# lane.net
KiCad netlist of a schematic drawn in Altium Designer
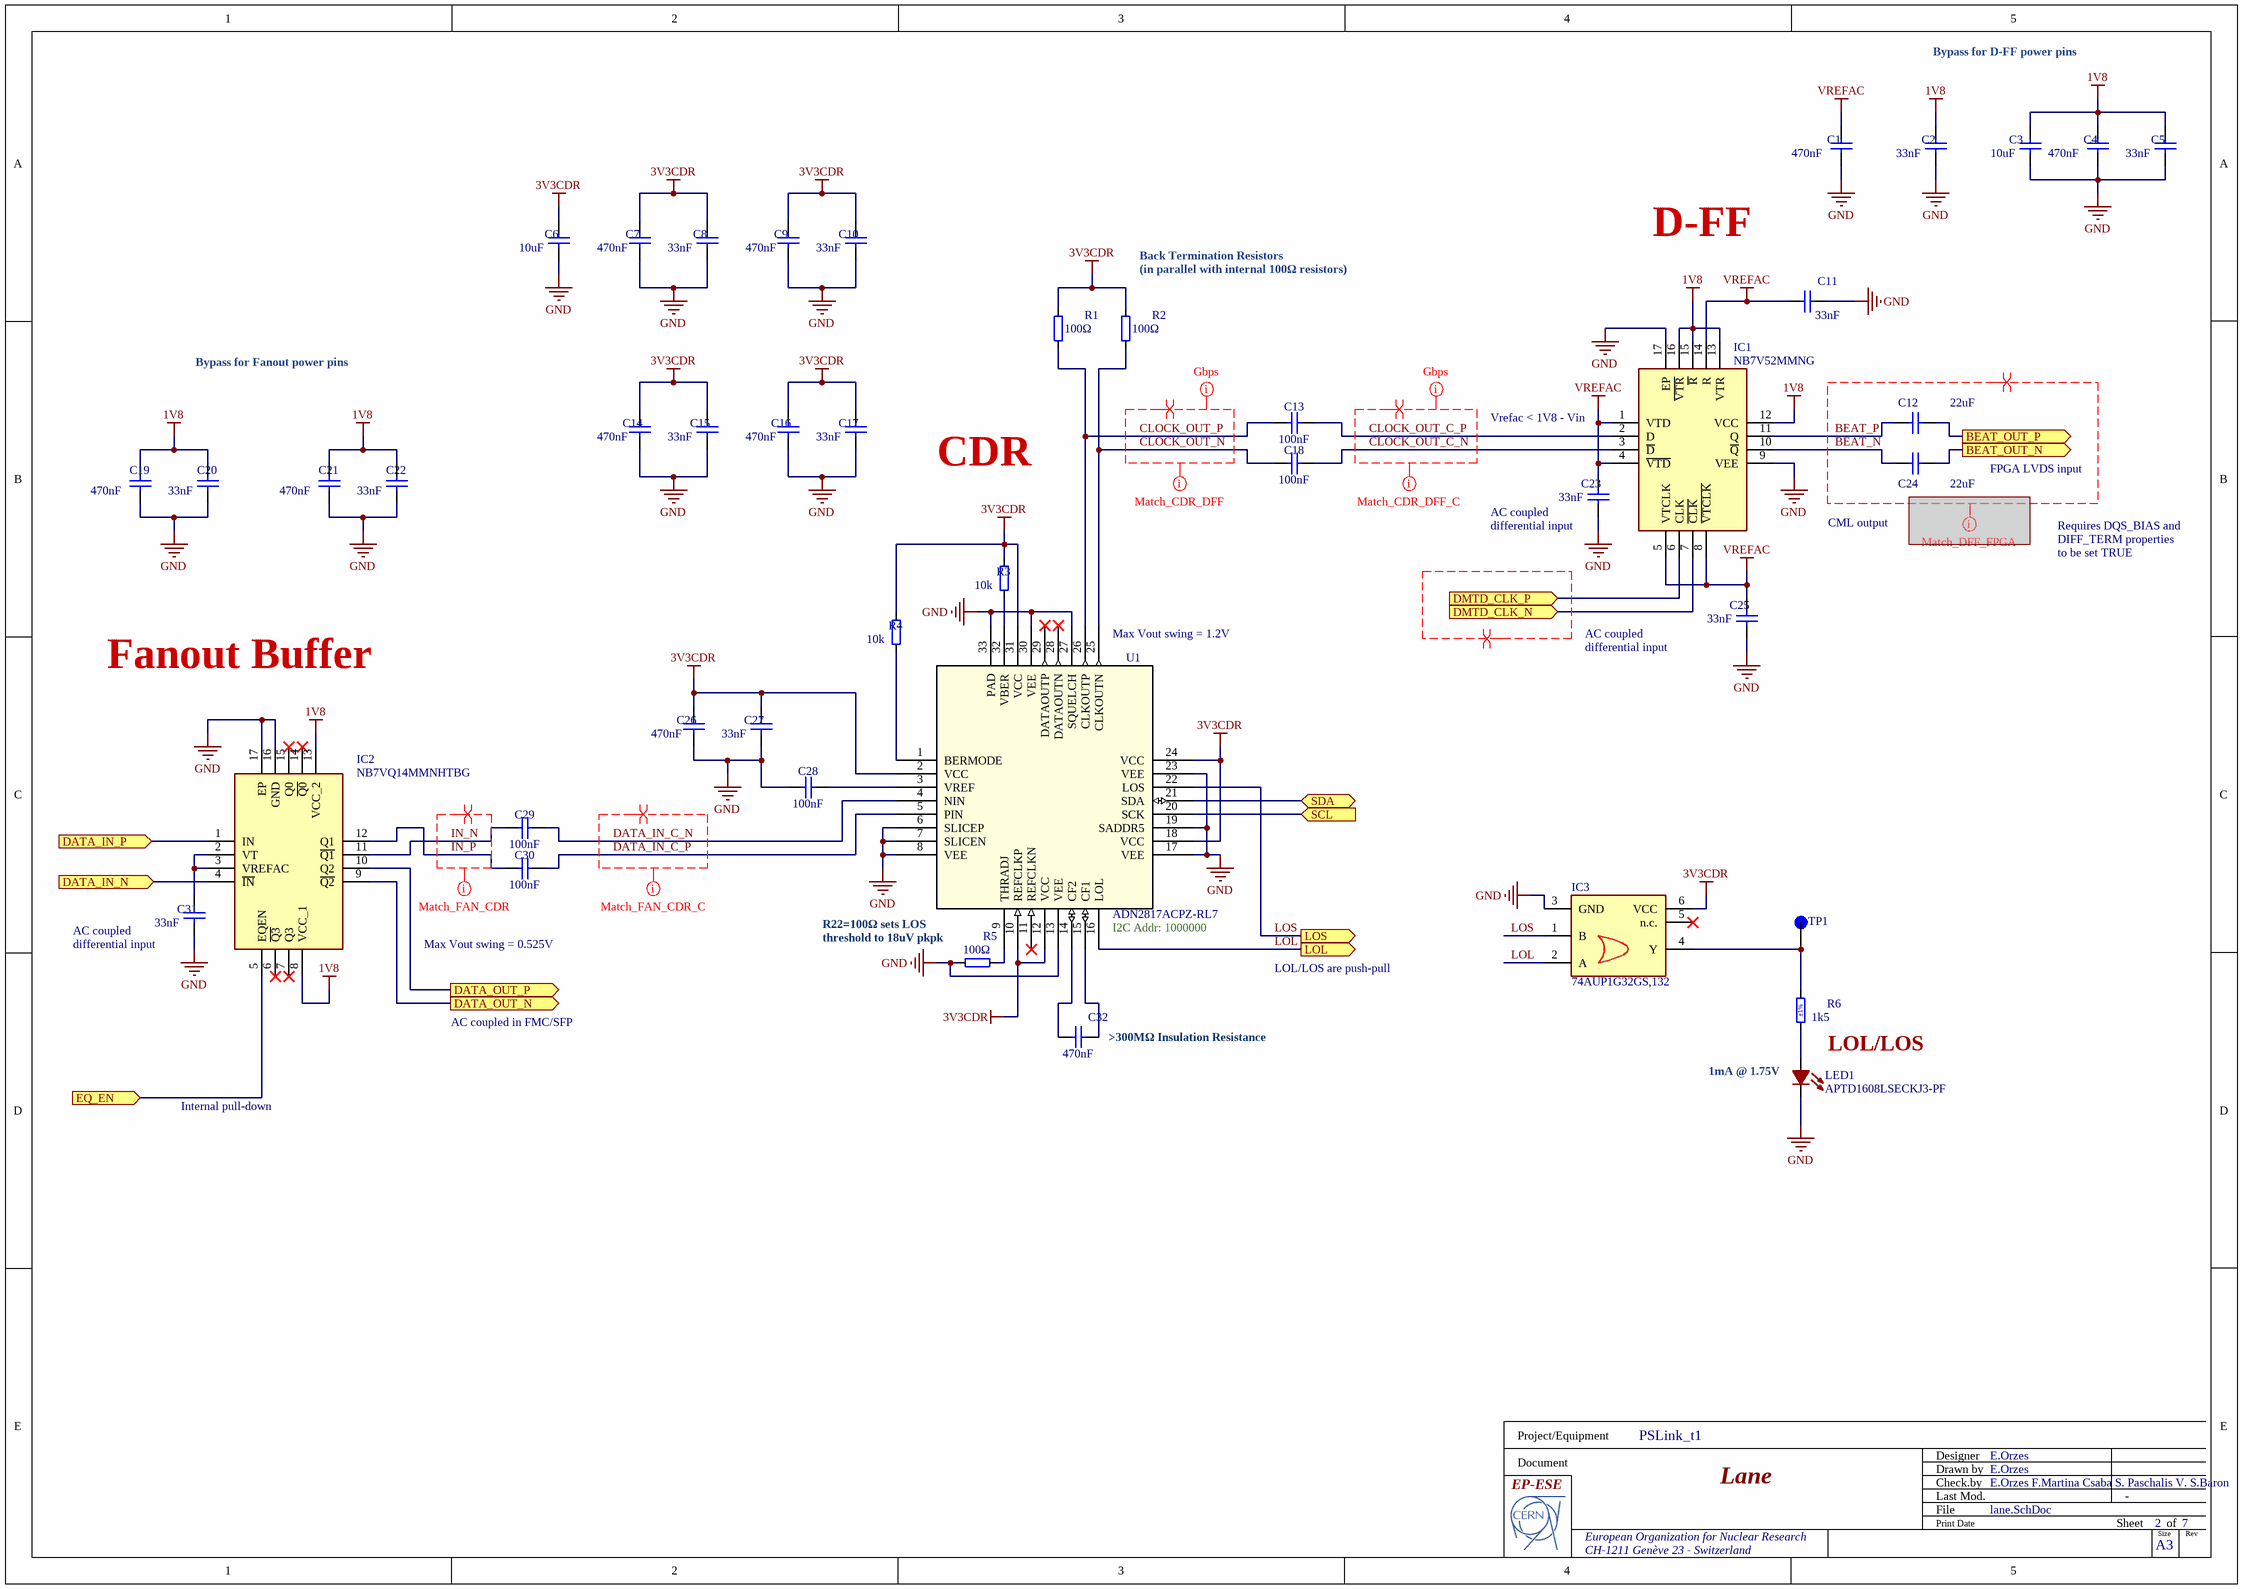
[diagram p0: lane.SchDoc]

(export (version "E")
  (design (tool "Eeschema 10.0.6"))
  (components
    (comp (ref "C1")
      (value "470nF")
      (footprint "CAPC0510X04N")
      (description "LLL153C70G474ME17")
      (libsource (lib "auxiliary_library") (part "Capacitor - non polarized"))
    )
    (comp (ref "C2")
      (value "33nF")
      (footprint "LLL03TR61E333KE01")
      (description "LLL03TR61E333KE01")
      (libsource (lib "auxiliary_library") (part "Capacitor - non polarized"))
    )
    (comp (ref "C3")
      (value "10uF")
      (footprint "CAPC1608X87N")
      (description "C1608X5R1E106M080AC")
      (fields
        (field (name "PART NUMBER") "CC0603_10UF_6.3V_20%_X5R")
        (field (name "VOLTAGE") "6.3V")
        (field (name "AUTHOR") "CERN DEM JLC")
      )
      (libsource (lib "Capacitors") (part "Capacitor - non polarized"))
    )
    (comp (ref "C4")
      (value "470nF")
      (footprint "CAPC0510X04N")
      (description "LLL153C70G474ME17")
      (libsource (lib "auxiliary_library") (part "Capacitor - non polarized"))
    )
    (comp (ref "C5")
      (value "33nF")
      (footprint "LLL03TR61E333KE01")
      (description "LLL03TR61E333KE01")
      (libsource (lib "auxiliary_library") (part "Capacitor - non polarized"))
    )
    (comp (ref "C6")
      (value "10uF")
      (footprint "CAPC1608X87N")
      (description "C1608X5R1E106M080AC")
      (fields
        (field (name "PART NUMBER") "CC0603_10UF_6.3V_20%_X5R")
        (field (name "VOLTAGE") "6.3V")
        (field (name "AUTHOR") "CERN DEM JLC")
      )
      (libsource (lib "Capacitors") (part "Capacitor - non polarized"))
    )
    (comp (ref "C7")
      (value "470nF")
      (footprint "CAPC0510X04N")
      (description "LLL153C70G474ME17")
      (libsource (lib "auxiliary_library") (part "Capacitor - non polarized"))
    )
    (comp (ref "C8")
      (value "33nF")
      (footprint "LLL03TR61E333KE01")
      (description "LLL03TR61E333KE01")
      (libsource (lib "auxiliary_library") (part "Capacitor - non polarized"))
    )
    (comp (ref "C9")
      (value "470nF")
      (footprint "CAPC0510X04N")
      (description "LLL153C70G474ME17")
      (libsource (lib "auxiliary_library") (part "Capacitor - non polarized"))
    )
    (comp (ref "C10")
      (value "33nF")
      (footprint "LLL03TR61E333KE01")
      (description "LLL03TR61E333KE01")
      (libsource (lib "auxiliary_library") (part "Capacitor - non polarized"))
    )
    (comp (ref "C11")
      (value "33nF")
      (footprint "LLL03TR61E333KE01")
      (description "LLL03TR61E333KE01")
      (libsource (lib "auxiliary_library") (part "Capacitor - non polarized"))
    )
    (comp (ref "C12")
      (value "22uF")
      (footprint "MURATA_HI_DENSITY_0402_CAP")
      (description "GRM155R60J226ME11")
      (libsource (lib "schLib") (part "C0402-22uF-high-density"))
    )
    (comp (ref "C13")
      (value "100nF")
      (footprint "MURATA_HI_DENSITY_0201")
      (description "GRM033R61C104KE14")
      (libsource (lib "schLib") (part "C0201-100nF-high-density"))
    )
    (comp (ref "C14")
      (value "470nF")
      (footprint "CAPC0510X04N")
      (description "LLL153C70G474ME17")
      (libsource (lib "auxiliary_library") (part "Capacitor - non polarized"))
    )
    (comp (ref "C15")
      (value "33nF")
      (footprint "LLL03TR61E333KE01")
      (description "LLL03TR61E333KE01")
      (libsource (lib "auxiliary_library") (part "Capacitor - non polarized"))
    )
    (comp (ref "C16")
      (value "470nF")
      (footprint "CAPC0510X04N")
      (description "LLL153C70G474ME17")
      (libsource (lib "auxiliary_library") (part "Capacitor - non polarized"))
    )
    (comp (ref "C17")
      (value "33nF")
      (footprint "LLL03TR61E333KE01")
      (description "LLL03TR61E333KE01")
      (libsource (lib "auxiliary_library") (part "Capacitor - non polarized"))
    )
    (comp (ref "C18")
      (value "100nF")
      (footprint "MURATA_HI_DENSITY_0201")
      (description "GRM033R61C104KE14")
      (libsource (lib "schLib") (part "C0201-100nF-high-density"))
    )
    (comp (ref "C19")
      (value "470nF")
      (footprint "CAPC0510X04N")
      (description "LLL153C70G474ME17")
      (libsource (lib "auxiliary_library") (part "Capacitor - non polarized"))
    )
    (comp (ref "C20")
      (value "33nF")
      (footprint "LLL03TR61E333KE01")
      (description "LLL03TR61E333KE01")
      (libsource (lib "auxiliary_library") (part "Capacitor - non polarized"))
    )
    (comp (ref "C21")
      (value "470nF")
      (footprint "CAPC0510X04N")
      (description "LLL153C70G474ME17")
      (libsource (lib "auxiliary_library") (part "Capacitor - non polarized"))
    )
    (comp (ref "C22")
      (value "33nF")
      (footprint "LLL03TR61E333KE01")
      (description "LLL03TR61E333KE01")
      (libsource (lib "auxiliary_library") (part "Capacitor - non polarized"))
    )
    (comp (ref "C23")
      (value "33nF")
      (footprint "LLL03TR61E333KE01")
      (description "LLL03TR61E333KE01")
      (libsource (lib "auxiliary_library") (part "Capacitor - non polarized"))
    )
    (comp (ref "C24")
      (value "22uF")
      (footprint "MURATA_HI_DENSITY_0402_CAP")
      (description "GRM155R60J226ME11")
      (libsource (lib "schLib") (part "C0402-22uF-high-density"))
    )
    (comp (ref "C25")
      (value "33nF")
      (footprint "LLL03TR61E333KE01")
      (description "LLL03TR61E333KE01")
      (libsource (lib "auxiliary_library") (part "Capacitor - non polarized"))
    )
    (comp (ref "C26")
      (value "470nF")
      (footprint "CAPC0510X04N")
      (description "LLL153C70G474ME17")
      (libsource (lib "auxiliary_library") (part "Capacitor - non polarized"))
    )
    (comp (ref "C27")
      (value "33nF")
      (footprint "LLL03TR61E333KE01")
      (description "LLL03TR61E333KE01")
      (libsource (lib "auxiliary_library") (part "Capacitor - non polarized"))
    )
    (comp (ref "C28")
      (value "100nF")
      (footprint "MURATA_HI_DENSITY_0201")
      (description "GRM033R61C104KE14")
      (libsource (lib "schLib") (part "C0201-100nF-high-density"))
    )
    (comp (ref "C29")
      (value "100nF")
      (footprint "MURATA_HI_DENSITY_0201")
      (description "GRM033R61C104KE14")
      (libsource (lib "schLib") (part "C0201-100nF-high-density"))
    )
    (comp (ref "C30")
      (value "100nF")
      (footprint "MURATA_HI_DENSITY_0201")
      (description "GRM033R61C104KE14")
      (libsource (lib "schLib") (part "C0201-100nF-high-density"))
    )
    (comp (ref "C31")
      (value "33nF")
      (footprint "LLL03TR61E333KE01")
      (description "LLL03TR61E333KE01")
      (libsource (lib "auxiliary_library") (part "Capacitor - non polarized"))
    )
    (comp (ref "C32")
      (value "470nF")
      (footprint "CAPC2013X140N")
      (description "GCM21BR71H474KA55L")
      (fields
        (field (name "PART NUMBER") "CC0805_470NF_50V_10%_X7R_MURATA_GCM21BR71H474KA55L")
        (field (name "VOLTAGE") "50V")
        (field (name "AUTHOR") "CERN DEM JLC")
      )
      (libsource (lib "Capacitors") (part "Capacitor - non polarized"))
    )
    (comp (ref "IC1")
      (value "NB7V52MMNG")
      (footprint "SamacSys:QFN50P300X300X100-17N")
      (description "Integrated Circuit")
      (fields (field (name "MOUSER PART NUMBER") "863-NB7V52MMNG"))
      (libsource (lib "SamacSys") (part "NB7V52MMNG"))
    )
    (comp (ref "IC2")
      (value "NB7VQ14MMNHTBG")
      (footprint "SamacSys:QFN50P300X300X100-17N")
      (description "Integrated Circuit")
      (fields (field (name "MOUSER PART NUMBER") "863-NB7VQ14MMNHTBG"))
      (libsource (lib "*") (part "NB7VQ14MMNHTBG"))
    )
    (comp (ref "IC3")
      (value "74AUP1G32GS,132")
      (footprint "SamacSys:74LVC1G3157GS132")
      (description "Integrated Circuit")
      (fields (field (name "MOUSER PART NUMBER") "771-74AUP1G32GS132"))
      (libsource (lib "SamacSys") (part "74AUP1G32GS,132"))
    )
    (comp (ref "LED1")
      (value "APTD1608LSECKJ3-PF")
      (footprint "APTD1608LSECKJ3-PF:LED_APTD1608LSECKJ3-PF_KNB")
      (description "Led Red 0603 2mA 1.8V 50mcd 84mW")
      (libsource (lib "APTD1608LSECKJ3-PF") (part "APTD1608LSECKJ3-PF"))
    )
    (comp (ref "R1")
      (value "100Ω")
      (footprint "MURATA_HI_DENSITY_0201")
      (description "Resistor")
      (libsource (lib "schLib") (part "R0201-100ohm-high-density"))
    )
    (comp (ref "R2")
      (value "100Ω")
      (footprint "MURATA_HI_DENSITY_0201")
      (description "Resistor")
      (libsource (lib "schLib") (part "R0201-100ohm-high-density"))
    )
    (comp (ref "R3")
      (value "10k")
      (footprint "MURATA_HI_DENSITY_0201")
      (description "Resistor 10k")
      (libsource (lib "schLib") (part "R0201-100ohm-high-density"))
    )
    (comp (ref "R4")
      (value "10k")
      (footprint "MURATA_HI_DENSITY_0201")
      (description "Resistor 10k")
      (libsource (lib "schLib") (part "R0201-100ohm-high-density"))
    )
    (comp (ref "R5")
      (value "100Ω")
      (footprint "MURATA_HI_DENSITY_0201")
      (description "Resistor")
      (libsource (lib "schLib") (part "R0201-100ohm-high-density"))
    )
    (comp (ref "R6")
      (value "1k5")
      (footprint "RESC1005X40N")
      (description "Resistor - 1%")
      (fields
        (field (name "TOLERANCE") "±1%")
        (field (name "PART NUMBER") "R0402_1K5_1%_0.0625W_100PPM")
        (field (name "POWER") "0.0625W")
        (field (name "AUTHOR") "CERN DEM JLC")
      )
      (libsource (lib "Resistors") (part "Resistor - 1%"))
    )
    (comp (ref "TP1")
      (value "RCU-0C")
      (footprint "TP+195X110")
      (fields (field (name "MF") "{'manufacturer': u'TE Connectivity AMP Connectors'}"))
      (libsource (lib "RCU-0C") (part "RCU-0C"))
    )
    (comp (ref "U1")
      (value "ADN2817ACPZ-RL7")
      (footprint "CP_32_11_ADI")
      (description "CDR")
      (libsource (lib "ADN2817ACPZ-RL7") (part "ADN2817ACPZ-RL7"))
    )
  )
  (nets
    (net (code "1") (name "/BEAT_N") (class "Default")
      (node (ref "C24") (pin "2") (pinfunction "2_2") (pintype "passive"))
      (node (ref "IC1") (pin "10") (pinfunction "~{Q}_10") (pintype "passive"))
    )
    (net (code "2") (name "/BEAT_OUT_N") (class "Default")
      (node (ref "C24") (pin "1") (pinfunction "1_1") (pintype "passive"))
    )
    (net (code "3") (name "/BEAT_OUT_P") (class "Default")
      (node (ref "C12") (pin "1") (pinfunction "1_1") (pintype "passive"))
    )
    (net (code "4") (name "/BEAT_P") (class "Default")
      (node (ref "C12") (pin "2") (pinfunction "2_2") (pintype "passive"))
      (node (ref "IC1") (pin "11") (pinfunction "Q_11") (pintype "passive"))
    )
    (net (code "5") (name "/CLOCK_OUT_C_N") (class "Default")
      (node (ref "C18") (pin "2") (pinfunction "2_2") (pintype "passive"))
      (node (ref "IC1") (pin "3") (pinfunction "~{D}_3") (pintype "passive"))
    )
    (net (code "6") (name "/CLOCK_OUT_C_P") (class "Default")
      (node (ref "C13") (pin "2") (pinfunction "2_2") (pintype "passive"))
      (node (ref "IC1") (pin "2") (pinfunction "D_2") (pintype "passive"))
    )
    (net (code "7") (name "/CLOCK_OUT_N") (class "Default")
      (node (ref "C18") (pin "1") (pinfunction "1_1") (pintype "passive"))
      (node (ref "R2") (pin "1") (pinfunction "1_1") (pintype "passive"))
      (node (ref "U1") (pin "25") (pinfunction "CLKOUTN_25") (pintype "output"))
    )
    (net (code "8") (name "/CLOCK_OUT_P") (class "Default")
      (node (ref "C13") (pin "1") (pinfunction "1_1") (pintype "passive"))
      (node (ref "R1") (pin "1") (pinfunction "1_1") (pintype "passive"))
      (node (ref "U1") (pin "26") (pinfunction "CLKOUTP_26") (pintype "output"))
    )
    (net (code "9") (name "/DATA_IN_C_N") (class "Default")
      (node (ref "C29") (pin "2") (pinfunction "2_2") (pintype "passive"))
      (node (ref "U1") (pin "4") (pinfunction "NIN_4") (pintype "passive"))
    )
    (net (code "10") (name "/DATA_IN_C_P") (class "Default")
      (node (ref "C30") (pin "2") (pinfunction "2_2") (pintype "passive"))
      (node (ref "U1") (pin "5") (pinfunction "PIN_5") (pintype "passive"))
    )
    (net (code "11") (name "/DATA_IN_N") (class "Default")
      (node (ref "IC2") (pin "4") (pinfunction "~{IN}_4") (pintype "passive"))
    )
    (net (code "12") (name "/DATA_IN_P") (class "Default")
      (node (ref "IC2") (pin "1") (pinfunction "IN_1") (pintype "passive"))
    )
    (net (code "13") (name "/DATA_OUT_N") (class "Default")
      (node (ref "IC2") (pin "9") (pinfunction "~{Q2}_9") (pintype "passive"))
    )
    (net (code "14") (name "/DATA_OUT_P") (class "Default")
      (node (ref "IC2") (pin "10") (pinfunction "Q2_10") (pintype "passive"))
    )
    (net (code "15") (name "/DMTD_CLK_N") (class "Default")
      (node (ref "IC1") (pin "7") (pinfunction "~{CLK}_7") (pintype "passive"))
    )
    (net (code "16") (name "/DMTD_CLK_P") (class "Default")
      (node (ref "IC1") (pin "6") (pinfunction "CLK_6") (pintype "passive"))
    )
    (net (code "17") (name "/EQ_EN") (class "Default")
      (node (ref "IC2") (pin "5") (pinfunction "EQEN_5") (pintype "passive"))
    )
    (net (code "18") (name "/IN_N") (class "Default")
      (node (ref "C29") (pin "1") (pinfunction "1_1") (pintype "passive"))
      (node (ref "IC2") (pin "11") (pinfunction "~{Q1}_11") (pintype "passive"))
    )
    (net (code "19") (name "/IN_P") (class "Default")
      (node (ref "C30") (pin "1") (pinfunction "1_1") (pintype "passive"))
      (node (ref "IC2") (pin "12") (pinfunction "Q1_12") (pintype "passive"))
    )
    (net (code "20") (name "/LOL") (class "Default")
      (node (ref "IC3") (pin "2") (pinfunction "A_2") (pintype "passive"))
      (node (ref "U1") (pin "16") (pinfunction "LOL_16") (pintype "passive"))
    )
    (net (code "21") (name "/LOS") (class "Default")
      (node (ref "IC3") (pin "1") (pinfunction "B_1") (pintype "passive"))
      (node (ref "U1") (pin "22") (pinfunction "LOS_22") (pintype "passive"))
    )
    (net (code "22") (name "/SCL") (class "Default")
      (node (ref "U1") (pin "20") (pinfunction "SCK_20") (pintype "passive"))
    )
    (net (code "23") (name "/SDA") (class "Default")
      (node (ref "U1") (pin "21") (pinfunction "SDA_21") (pintype "bidirectional"))
    )
    (net (code "24") (name "1V8") (class "Default")
      (node (ref "C19") (pin "2") (pinfunction "2_2") (pintype "passive"))
      (node (ref "C2") (pin "2") (pinfunction "2_2") (pintype "passive"))
      (node (ref "C20") (pin "2") (pinfunction "2_2") (pintype "passive"))
      (node (ref "C21") (pin "2") (pinfunction "2_2") (pintype "passive"))
      (node (ref "C22") (pin "2") (pinfunction "2_2") (pintype "passive"))
      (node (ref "C3") (pin "2") (pinfunction "2_2") (pintype "passive"))
      (node (ref "C4") (pin "2") (pinfunction "2_2") (pintype "passive"))
      (node (ref "C5") (pin "2") (pinfunction "2_2") (pintype "passive"))
      (node (ref "IC1") (pin "12") (pinfunction "VCC_12") (pintype "passive"))
      (node (ref "IC1") (pin "13") (pinfunction "VTR_13") (pintype "passive"))
      (node (ref "IC1") (pin "15") (pinfunction "~{R}_15") (pintype "passive"))
      (node (ref "IC1") (pin "16") (pinfunction "~{VTR}_16") (pintype "passive"))
      (node (ref "IC2") (pin "13") (pinfunction "VCC_2_13") (pintype "passive"))
      (node (ref "IC2") (pin "8") (pinfunction "VCC_1_8") (pintype "passive"))
    )
    (net (code "25") (name "3V3CDR") (class "Default")
      (node (ref "C10") (pin "2") (pinfunction "2_2") (pintype "passive"))
      (node (ref "C14") (pin "2") (pinfunction "2_2") (pintype "passive"))
      (node (ref "C15") (pin "2") (pinfunction "2_2") (pintype "passive"))
      (node (ref "C16") (pin "2") (pinfunction "2_2") (pintype "passive"))
      (node (ref "C17") (pin "2") (pinfunction "2_2") (pintype "passive"))
      (node (ref "C26") (pin "2") (pinfunction "2_2") (pintype "passive"))
      (node (ref "C27") (pin "2") (pinfunction "2_2") (pintype "passive"))
      (node (ref "C6") (pin "2") (pinfunction "2_2") (pintype "passive"))
      (node (ref "C7") (pin "2") (pinfunction "2_2") (pintype "passive"))
      (node (ref "C8") (pin "2") (pinfunction "2_2") (pintype "passive"))
      (node (ref "C9") (pin "2") (pinfunction "2_2") (pintype "passive"))
      (node (ref "IC3") (pin "6") (pinfunction "VCC_6") (pintype "passive"))
      (node (ref "R1") (pin "2") (pinfunction "2_2") (pintype "passive"))
      (node (ref "R2") (pin "2") (pinfunction "2_2") (pintype "passive"))
      (node (ref "R3") (pin "2") (pinfunction "2_2") (pintype "passive"))
      (node (ref "R4") (pin "2") (pinfunction "2_2") (pintype "passive"))
      (node (ref "U1") (pin "10") (pinfunction "REFCLKP_10") (pintype "input"))
      (node (ref "U1") (pin "12") (pinfunction "VCC_12") (pintype "power_in"))
      (node (ref "U1") (pin "18") (pinfunction "VCC_18") (pintype "power_in"))
      (node (ref "U1") (pin "2") (pinfunction "VCC_2") (pintype "power_in"))
      (node (ref "U1") (pin "24") (pinfunction "VCC_24") (pintype "power_in"))
      (node (ref "U1") (pin "31") (pinfunction "VCC_31") (pintype "power_in"))
    )
    (net (code "26") (name "GND") (class "Default")
      (node (ref "C1") (pin "1") (pinfunction "1_1") (pintype "passive"))
      (node (ref "C10") (pin "1") (pinfunction "1_1") (pintype "passive"))
      (node (ref "C11") (pin "1") (pinfunction "1_1") (pintype "passive"))
      (node (ref "C14") (pin "1") (pinfunction "1_1") (pintype "passive"))
      (node (ref "C15") (pin "1") (pinfunction "1_1") (pintype "passive"))
      (node (ref "C16") (pin "1") (pinfunction "1_1") (pintype "passive"))
      (node (ref "C17") (pin "1") (pinfunction "1_1") (pintype "passive"))
      (node (ref "C19") (pin "1") (pinfunction "1_1") (pintype "passive"))
      (node (ref "C2") (pin "1") (pinfunction "1_1") (pintype "passive"))
      (node (ref "C20") (pin "1") (pinfunction "1_1") (pintype "passive"))
      (node (ref "C21") (pin "1") (pinfunction "1_1") (pintype "passive"))
      (node (ref "C22") (pin "1") (pinfunction "1_1") (pintype "passive"))
      (node (ref "C23") (pin "1") (pinfunction "1_1") (pintype "passive"))
      (node (ref "C25") (pin "1") (pinfunction "1_1") (pintype "passive"))
      (node (ref "C26") (pin "1") (pinfunction "1_1") (pintype "passive"))
      (node (ref "C27") (pin "1") (pinfunction "1_1") (pintype "passive"))
      (node (ref "C28") (pin "1") (pinfunction "1_1") (pintype "passive"))
      (node (ref "C3") (pin "1") (pinfunction "1_1") (pintype "passive"))
      (node (ref "C31") (pin "1") (pinfunction "1_1") (pintype "passive"))
      (node (ref "C4") (pin "1") (pinfunction "1_1") (pintype "passive"))
      (node (ref "C5") (pin "1") (pinfunction "1_1") (pintype "passive"))
      (node (ref "C6") (pin "1") (pinfunction "1_1") (pintype "passive"))
      (node (ref "C7") (pin "1") (pinfunction "1_1") (pintype "passive"))
      (node (ref "C8") (pin "1") (pinfunction "1_1") (pintype "passive"))
      (node (ref "C9") (pin "1") (pinfunction "1_1") (pintype "passive"))
      (node (ref "IC1") (pin "17") (pinfunction "EP_17") (pintype "passive"))
      (node (ref "IC1") (pin "9") (pinfunction "VEE_9") (pintype "passive"))
      (node (ref "IC2") (pin "16") (pinfunction "GND_16") (pintype "passive"))
      (node (ref "IC2") (pin "17") (pinfunction "EP_17") (pintype "passive"))
      (node (ref "IC3") (pin "3") (pinfunction "GND_3") (pintype "passive"))
      (node (ref "LED1") (pin "1") (pinfunction "C_1") (pintype "passive"))
      (node (ref "R5") (pin "1") (pinfunction "1_1") (pintype "passive"))
      (node (ref "U1") (pin "13") (pinfunction "VEE_13") (pintype "power_in"))
      (node (ref "U1") (pin "17") (pinfunction "VEE_17") (pintype "power_in"))
      (node (ref "U1") (pin "19") (pinfunction "SADDR5_19") (pintype "passive"))
      (node (ref "U1") (pin "23") (pinfunction "VEE_23") (pintype "power_in"))
      (node (ref "U1") (pin "27") (pinfunction "SQUELCH_27") (pintype "passive"))
      (node (ref "U1") (pin "30") (pinfunction "VEE_30") (pintype "power_in"))
      (node (ref "U1") (pin "33") (pinfunction "PAD_33") (pintype "power_in"))
      (node (ref "U1") (pin "6") (pinfunction "SLICEP_6") (pintype "passive"))
      (node (ref "U1") (pin "7") (pinfunction "SLICEN_7") (pintype "passive"))
      (node (ref "U1") (pin "8") (pinfunction "VEE_8") (pintype "power_in"))
    )
    (net (code "27") (name "Net-(IC2-VREFAC)") (class "Default")
      (node (ref "C31") (pin "2") (pinfunction "2_2") (pintype "passive"))
      (node (ref "IC2") (pin "2") (pinfunction "VT_2") (pintype "passive"))
      (node (ref "IC2") (pin "3") (pinfunction "VREFAC_3") (pintype "passive"))
    )
    (net (code "28") (name "Net-(IC3-Y)") (class "Default")
      (node (ref "IC3") (pin "4") (pinfunction "Y_4") (pintype "passive"))
      (node (ref "R6") (pin "2") (pinfunction "2_2") (pintype "passive"))
      (node (ref "TP1") (pin "1") (pinfunction "TP_1") (pintype "passive"))
    )
    (net (code "29") (name "Net-(LED1-A)") (class "Default")
      (node (ref "LED1") (pin "2") (pinfunction "A_2") (pintype "passive"))
      (node (ref "R6") (pin "1") (pinfunction "1_1") (pintype "passive"))
    )
    (net (code "30") (name "Net-(U1-BERMODE)") (class "Default")
      (node (ref "R4") (pin "1") (pinfunction "1_1") (pintype "passive"))
      (node (ref "U1") (pin "1") (pinfunction "BERMODE_1") (pintype "passive"))
    )
    (net (code "31") (name "Net-(U1-CF1)") (class "Default")
      (node (ref "C32") (pin "2") (pinfunction "2_2") (pintype "passive"))
      (node (ref "U1") (pin "15") (pinfunction "CF1_15") (pintype "bidirectional"))
    )
    (net (code "32") (name "Net-(U1-CF2)") (class "Default")
      (node (ref "C32") (pin "1") (pinfunction "1_1") (pintype "passive"))
      (node (ref "U1") (pin "14") (pinfunction "CF2_14") (pintype "bidirectional"))
    )
    (net (code "33") (name "Net-(U1-THRADJ)") (class "Default")
      (node (ref "R5") (pin "2") (pinfunction "2_2") (pintype "passive"))
      (node (ref "U1") (pin "9") (pinfunction "THRADJ_9") (pintype "passive"))
    )
    (net (code "34") (name "Net-(U1-VBER)") (class "Default")
      (node (ref "R3") (pin "1") (pinfunction "1_1") (pintype "passive"))
      (node (ref "U1") (pin "32") (pinfunction "VBER_32") (pintype "passive"))
    )
    (net (code "35") (name "Net-(U1-VREF)") (class "Default")
      (node (ref "C28") (pin "2") (pinfunction "2_2") (pintype "passive"))
      (node (ref "U1") (pin "3") (pinfunction "VREF_3") (pintype "power_in"))
    )
    (net (code "36") (name "VREFAC") (class "Default")
      (node (ref "C1") (pin "2") (pinfunction "2_2") (pintype "passive"))
      (node (ref "C11") (pin "2") (pinfunction "2_2") (pintype "passive"))
      (node (ref "C23") (pin "2") (pinfunction "2_2") (pintype "passive"))
      (node (ref "C25") (pin "2") (pinfunction "2_2") (pintype "passive"))
      (node (ref "IC1") (pin "1") (pinfunction "VTD_1") (pintype "passive"))
      (node (ref "IC1") (pin "14") (pinfunction "R_14") (pintype "passive"))
      (node (ref "IC1") (pin "4") (pinfunction "~{VTD}_4") (pintype "passive"))
      (node (ref "IC1") (pin "5") (pinfunction "VTCLK_5") (pintype "passive"))
      (node (ref "IC1") (pin "8") (pinfunction "~{VTCLK}_8") (pintype "passive"))
    )
    (net (code "37") (name "unconnected-(IC2-Q0-Pad15)") (class "Default")
      (node (ref "IC2") (pin "15") (pinfunction "Q0_15") (pintype "passive+no_connect"))
    )
    (net (code "38") (name "unconnected-(IC2-Q3-Pad7)") (class "Default")
      (node (ref "IC2") (pin "7") (pinfunction "Q3_7") (pintype "passive+no_connect"))
    )
    (net (code "39") (name "unconnected-(IC2-~{Q0}-Pad14)") (class "Default")
      (node (ref "IC2") (pin "14") (pinfunction "~{Q0}_14") (pintype "passive+no_connect"))
    )
    (net (code "40") (name "unconnected-(IC2-~{Q3}-Pad6)") (class "Default")
      (node (ref "IC2") (pin "6") (pinfunction "~{Q3}_6") (pintype "passive+no_connect"))
    )
    (net (code "41") (name "unconnected-(IC3-n.c.-Pad5)") (class "Default")
      (node (ref "IC3") (pin "5") (pinfunction "n.c._5") (pintype "passive+no_connect"))
    )
    (net (code "42") (name "unconnected-(U1-DATAOUTN-Pad28)") (class "Default")
      (node (ref "U1") (pin "28") (pinfunction "DATAOUTN_28") (pintype "output+no_connect"))
    )
    (net (code "43") (name "unconnected-(U1-DATAOUTP-Pad29)") (class "Default")
      (node (ref "U1") (pin "29") (pinfunction "DATAOUTP_29") (pintype "output+no_connect"))
    )
    (net (code "44") (name "unconnected-(U1-REFCLKN-Pad11)") (class "Default")
      (node (ref "U1") (pin "11") (pinfunction "REFCLKN_11") (pintype "input+no_connect"))
    )
  )
)
